# RS232_ACPL_827.net
KiCad netlist of a schematic drawn in EAGLE
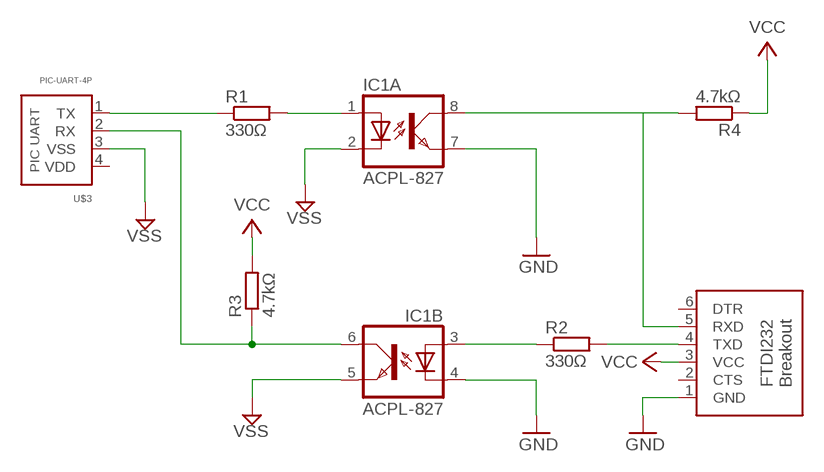
[diagram p0: schematic, sheet 1]

(export (version "E")
  (design (tool "Eeschema 10.0.6"))
  (components
    (comp (ref "IC1")
      (value "ACPL-827")
      (footprint "eagle-import:DIL08")
      (libsource (lib "eagle-import") (part "ACPL-827"))
    )
    (comp (ref "R1")
      (value "330Ω")
      (footprint "eagle-import:0207_10")
      (libsource (lib "eagle-import") (part "R-EU_0207/10"))
    )
    (comp (ref "R2")
      (value "330Ω")
      (footprint "eagle-import:0204_7")
      (libsource (lib "eagle-import") (part "R-EU_0204/7"))
    )
    (comp (ref "R3")
      (value "4.7kΩ")
      (footprint "eagle-import:0204_7")
      (libsource (lib "eagle-import") (part "R-EU_0204/7"))
    )
    (comp (ref "R4")
      (value "4.7kΩ")
      (footprint "eagle-import:0204_7")
      (libsource (lib "eagle-import") (part "R-EU_0204/7"))
    )
    (comp (ref "U$2")
      (value "FTDI232-BO-6P")
      (footprint "eagle-import:CONN-6P")
      (libsource (lib "eagle-import") (part "FTDI232-BO-6P"))
    )
    (comp (ref "U$3")
      (value "PIC-UART-4P")
      (footprint "eagle-import:CONN-4P")
      (libsource (lib "eagle-import") (part "PIC-UART-4P"))
    )
  )
  (nets
    (net (code "1") (name "GND") (class "Default")
      (node (ref "IC1") (pin "4") (pinfunction "C_4") (pintype "passive"))
      (node (ref "IC1") (pin "7") (pinfunction "EMIT_7") (pintype "passive"))
      (node (ref "U$2") (pin "1") (pinfunction "GND_1") (pintype "bidirectional"))
    )
    (net (code "2") (name "Net-(IC1A-A)") (class "Default")
      (node (ref "IC1") (pin "1") (pinfunction "A_1") (pintype "passive"))
      (node (ref "R1") (pin "2") (pinfunction "2_2") (pintype "passive"))
    )
    (net (code "3") (name "Net-(IC1A-COL)") (class "Default")
      (node (ref "IC1") (pin "8") (pinfunction "COL_8") (pintype "passive"))
      (node (ref "R4") (pin "2") (pinfunction "2_2") (pintype "passive"))
      (node (ref "U$2") (pin "5") (pinfunction "RXD_5") (pintype "bidirectional"))
    )
    (net (code "4") (name "Net-(IC1B-A)") (class "Default")
      (node (ref "IC1") (pin "3") (pinfunction "A_3") (pintype "passive"))
      (node (ref "R2") (pin "1") (pinfunction "1_1") (pintype "passive"))
    )
    (net (code "5") (name "Net-(IC1B-COL)") (class "Default")
      (node (ref "IC1") (pin "6") (pinfunction "COL_6") (pintype "passive"))
      (node (ref "R3") (pin "1") (pinfunction "1_1") (pintype "passive"))
      (node (ref "U$3") (pin "2") (pinfunction "RX_2") (pintype "passive"))
    )
    (net (code "6") (name "Net-(U$2-TXD)") (class "Default")
      (node (ref "R2") (pin "2") (pinfunction "2_2") (pintype "passive"))
      (node (ref "U$2") (pin "4") (pinfunction "TXD_4") (pintype "bidirectional"))
    )
    (net (code "7") (name "Net-(U$3-TX)") (class "Default")
      (node (ref "R1") (pin "1") (pinfunction "1_1") (pintype "passive"))
      (node (ref "U$3") (pin "1") (pinfunction "TX_1") (pintype "passive"))
    )
    (net (code "8") (name "VCC") (class "Default")
      (node (ref "R3") (pin "2") (pinfunction "2_2") (pintype "passive"))
      (node (ref "R4") (pin "1") (pinfunction "1_1") (pintype "passive"))
      (node (ref "U$2") (pin "3") (pinfunction "VCC_3") (pintype "bidirectional"))
    )
    (net (code "9") (name "VSS") (class "Default")
      (node (ref "IC1") (pin "2") (pinfunction "C_2") (pintype "passive"))
      (node (ref "IC1") (pin "5") (pinfunction "EMIT_5") (pintype "passive"))
      (node (ref "U$3") (pin "3") (pinfunction "VSS_3") (pintype "passive"))
    )
    (net (code "10") (name "unconnected-(U$2-CTS-Pad2)") (class "Default")
      (node (ref "U$2") (pin "2") (pinfunction "CTS_2") (pintype "bidirectional"))
    )
    (net (code "11") (name "unconnected-(U$2-DTR-Pad6)") (class "Default")
      (node (ref "U$2") (pin "6") (pinfunction "DTR_6") (pintype "bidirectional"))
    )
    (net (code "12") (name "unconnected-(U$3-VDD-Pad4)") (class "Default")
      (node (ref "U$3") (pin "4") (pinfunction "VDD_4") (pintype "passive"))
    )
  )
)
